# SeptinaryAI_Balldi__elec_mother_board__m.net
KiCad netlist of a schematic drawn in Altium Designer
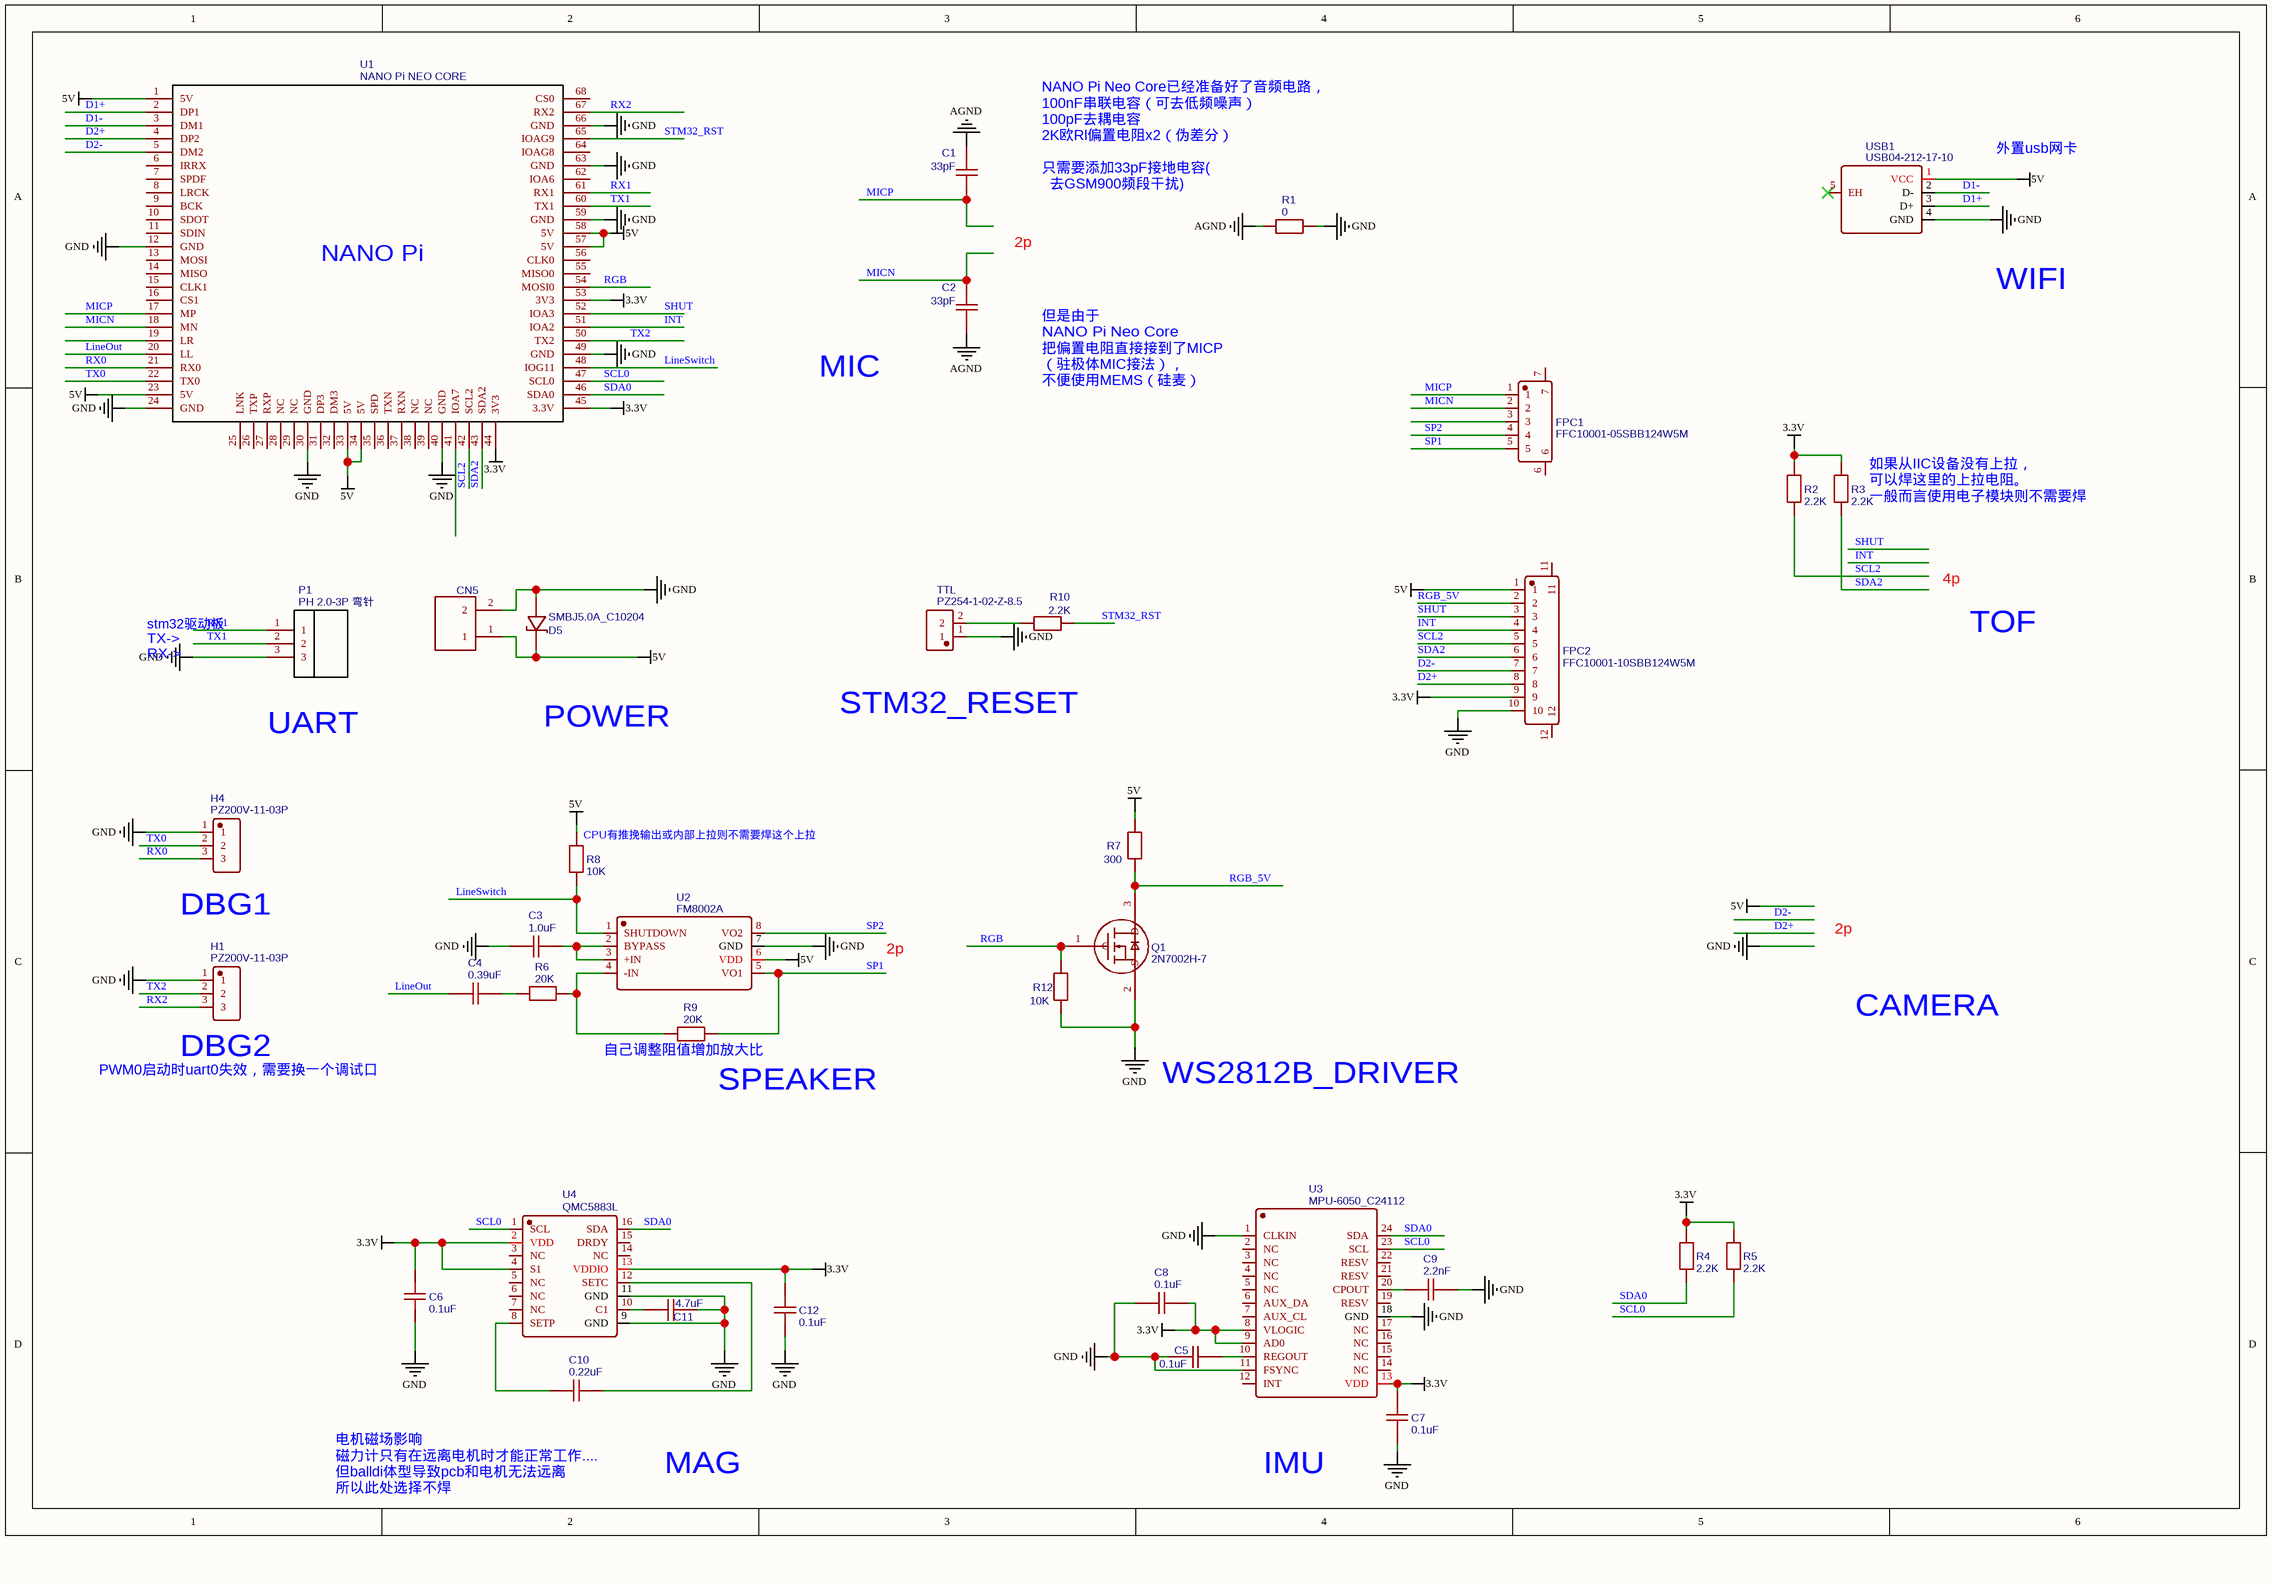
[diagram p0: SeptinaryAI_Balldi__elec_mother_board__mother_board_2023-07-21.schdoc]

(export (version "E")
  (design (tool "Eeschema 10.0.6"))
  (components
    (comp (ref "C1")
      (value "33pF")
      (fields
        (field (name "BOM_SUPPLIER PART") "C2762283")
        (field (name "BOM_MANUFACTURER PART") "CL10F104ZO8NNNC")
        (field (name "CONTRIBUTOR") "LCSC")
      )
      (libsource (lib "altium-import") (part "root_1_33pF_"))
    )
    (comp (ref "C2")
      (value "33pF")
      (fields
        (field (name "BOM_SUPPLIER PART") "C2762283")
        (field (name "BOM_MANUFACTURER PART") "CL10F104ZO8NNNC")
        (field (name "CONTRIBUTOR") "LCSC")
      )
      (libsource (lib "altium-import") (part "root_1_33pF_"))
    )
    (comp (ref "C3")
      (value "1.0uF")
      (fields
        (field (name "BOM_SUPPLIER PART") "C2762283")
        (field (name "BOM_MANUFACTURER PART") "CL10F104ZO8NNNC")
        (field (name "CONTRIBUTOR") "LCSC")
      )
      (libsource (lib "altium-import") (part "root_2_1.0uF_"))
    )
    (comp (ref "C4")
      (value "0.39uF")
      (fields
        (field (name "BOM_SUPPLIER PART") "C2762283")
        (field (name "BOM_MANUFACTURER PART") "CL10F104ZO8NNNC")
        (field (name "CONTRIBUTOR") "LCSC")
      )
      (libsource (lib "altium-import") (part "root_2_0.39uF_"))
    )
    (comp (ref "C5")
      (value "0.1uF")
      (fields
        (field (name "BOM_SUPPLIER PART") "C2762283")
        (field (name "BOM_MANUFACTURER PART") "CL10F104ZO8NNNC")
        (field (name "CONTRIBUTOR") "LCSC")
      )
      (libsource (lib "altium-import") (part "root_2_0.1uF_"))
    )
    (comp (ref "C6")
      (value "0.1uF")
      (fields
        (field (name "BOM_SUPPLIER PART") "C2762283")
        (field (name "BOM_MANUFACTURER PART") "CL10F104ZO8NNNC")
        (field (name "CONTRIBUTOR") "LCSC")
      )
      (libsource (lib "altium-import") (part "root_3_0.1uF_"))
    )
    (comp (ref "C7")
      (value "0.1uF")
      (fields
        (field (name "BOM_SUPPLIER PART") "C2762283")
        (field (name "BOM_MANUFACTURER PART") "CL10F104ZO8NNNC")
        (field (name "CONTRIBUTOR") "LCSC")
      )
      (libsource (lib "altium-import") (part "root_3_0.1uF_"))
    )
    (comp (ref "C8")
      (value "0.1uF")
      (fields
        (field (name "BOM_SUPPLIER PART") "C2762283")
        (field (name "BOM_MANUFACTURER PART") "CL10F104ZO8NNNC")
        (field (name "CONTRIBUTOR") "LCSC")
      )
      (libsource (lib "altium-import") (part "root_0_0.1uF_"))
    )
    (comp (ref "C9")
      (value "2.2nF")
      (fields
        (field (name "BOM_SUPPLIER PART") "C2762283")
        (field (name "BOM_MANUFACTURER PART") "CL10F104ZO8NNNC")
        (field (name "CONTRIBUTOR") "LCSC")
      )
      (libsource (lib "altium-import") (part "root_0_2.2nF_"))
    )
    (comp (ref "C10")
      (value "0.22uF")
      (fields
        (field (name "BOM_SUPPLIER PART") "C2762283")
        (field (name "BOM_MANUFACTURER PART") "CL10F104ZO8NNNC")
        (field (name "CONTRIBUTOR") "LCSC")
      )
      (libsource (lib "altium-import") (part "root_0_0.22uF_"))
    )
    (comp (ref "C11")
      (value "4.7uF")
      (fields
        (field (name "BOM_SUPPLIER PART") "C2762283")
        (field (name "BOM_MANUFACTURER PART") "CL10F104ZO8NNNC")
        (field (name "CONTRIBUTOR") "LCSC")
      )
      (libsource (lib "altium-import") (part "root_0_4.7uF_"))
    )
    (comp (ref "C12")
      (value "0.1uF")
      (fields
        (field (name "BOM_SUPPLIER PART") "C2762283")
        (field (name "BOM_MANUFACTURER PART") "CL10F104ZO8NNNC")
        (field (name "CONTRIBUTOR") "LCSC")
      )
      (libsource (lib "altium-import") (part "root_3_0.1uF_"))
    )
    (comp (ref "CN5")
      (value "640454-2")
      (fields (field (name "BOM_SUPPLIER PART") "C86501"))
      (libsource (lib "altium-import") (part "root_2_640454-2_"))
    )
    (comp (ref "D5")
      (value "SMBJ5.0A_C10204")
      (fields (field (name "BOM_MANUFACTURER PART") "SMBJ5.0A") (field (name "BOM_SUPPLIER PART") "C10204"))
      (libsource (lib "altium-import") (part "root_1_SMBJ5.0A_C10204_"))
    )
    (comp (ref "FPC1")
      (value "FFC10001-05SBB124W5M")
      (fields (field (name "BOM_SUPPLIER PART") "C2833987") (field (name "CONTRIBUTOR") "LCSC"))
      (libsource (lib "altium-import") (part "root_0_FFC10001-05SBB124W5M_"))
    )
    (comp (ref "FPC2")
      (value "FFC10001-10SBB124W5M")
      (fields (field (name "BOM_SUPPLIER PART") "C456461") (field (name "CONTRIBUTOR") "LCSC"))
      (libsource (lib "altium-import") (part "root_0_FFC10001-10SBB124W5M_"))
    )
    (comp (ref "H1")
      (value "PZ200V-11-03P")
      (fields (field (name "BOM_SUPPLIER PART") "C541857") (field (name "CONTRIBUTOR") "LCSC"))
      (libsource (lib "altium-import") (part "root_0_PZ200V-11-03P_"))
    )
    (comp (ref "H4")
      (value "PZ200V-11-03P")
      (fields (field (name "BOM_SUPPLIER PART") "C541857") (field (name "CONTRIBUTOR") "LCSC"))
      (libsource (lib "altium-import") (part "root_0_PZ200V-11-03P_"))
    )
    (comp (ref "P1")
      (value "PH 2.0-3P 弯针")
      (fields (field (name "BOM_MANUFACTURER PART") "PH 2.0-3P") (field (name "CONTRIBUTOR") "584992092"))
      (libsource (lib "altium-import") (part "root_3_PH 2.0-3P 弯针_"))
    )
    (comp (ref "Q1")
      (value "2N7002H-7")
      (fields (field (name "BOM_SUPPLIER PART") "C150714") (field (name "CONTRIBUTOR") "LCSC"))
      (libsource (lib "altium-import") (part "root_0_2N7002H-7_"))
    )
    (comp (ref "R1")
      (value "0")
      (fields
        (field (name "BOM_SUPPLIER PART") "C1870287")
        (field (name "BOM_MANUFACTURER PART") "TNPW0603130RBEEA")
        (field (name "CONTRIBUTOR") "LCSC")
      )
      (libsource (lib "altium-import") (part "root_0_0_"))
    )
    (comp (ref "R2")
      (value "2.2K")
      (fields
        (field (name "BOM_SUPPLIER PART") "C1870287")
        (field (name "BOM_MANUFACTURER PART") "TNPW0603130RBEEA")
        (field (name "CONTRIBUTOR") "LCSC")
      )
      (libsource (lib "altium-import") (part "root_3_2.2K_"))
    )
    (comp (ref "R3")
      (value "2.2K")
      (fields
        (field (name "BOM_SUPPLIER PART") "C1870287")
        (field (name "BOM_MANUFACTURER PART") "TNPW0603130RBEEA")
        (field (name "CONTRIBUTOR") "LCSC")
      )
      (libsource (lib "altium-import") (part "root_3_2.2K_"))
    )
    (comp (ref "R4")
      (value "2.2K")
      (fields
        (field (name "BOM_SUPPLIER PART") "C1870287")
        (field (name "BOM_MANUFACTURER PART") "TNPW0603130RBEEA")
        (field (name "CONTRIBUTOR") "LCSC")
      )
      (libsource (lib "altium-import") (part "root_3_2.2K_"))
    )
    (comp (ref "R5")
      (value "2.2K")
      (fields
        (field (name "BOM_SUPPLIER PART") "C1870287")
        (field (name "BOM_MANUFACTURER PART") "TNPW0603130RBEEA")
        (field (name "CONTRIBUTOR") "LCSC")
      )
      (libsource (lib "altium-import") (part "root_3_2.2K_"))
    )
    (comp (ref "R6")
      (value "20K")
      (fields
        (field (name "BOM_SUPPLIER PART") "C1870287")
        (field (name "BOM_MANUFACTURER PART") "TNPW0603130RBEEA")
        (field (name "CONTRIBUTOR") "LCSC")
      )
      (libsource (lib "altium-import") (part "root_0_20K_"))
    )
    (comp (ref "R7")
      (value "300")
      (fields
        (field (name "BOM_SUPPLIER PART") "C1870287")
        (field (name "BOM_MANUFACTURER PART") "TNPW0603130RBEEA")
        (field (name "CONTRIBUTOR") "LCSC")
      )
      (libsource (lib "altium-import") (part "root_3_300_"))
    )
    (comp (ref "R8")
      (value "10K")
      (fields
        (field (name "BOM_SUPPLIER PART") "C1870287")
        (field (name "BOM_MANUFACTURER PART") "TNPW0603130RBEEA")
        (field (name "CONTRIBUTOR") "LCSC")
      )
      (libsource (lib "altium-import") (part "root_1_10K_"))
    )
    (comp (ref "R9")
      (value "20K")
      (fields
        (field (name "BOM_SUPPLIER PART") "C1870287")
        (field (name "BOM_MANUFACTURER PART") "TNPW0603130RBEEA")
        (field (name "CONTRIBUTOR") "LCSC")
      )
      (libsource (lib "altium-import") (part "root_0_20K_"))
    )
    (comp (ref "R10")
      (value "2.2K")
      (fields
        (field (name "BOM_SUPPLIER PART") "C1870287")
        (field (name "BOM_MANUFACTURER PART") "TNPW0603130RBEEA")
        (field (name "CONTRIBUTOR") "LCSC")
      )
      (libsource (lib "altium-import") (part "root_0_2.2K_"))
    )
    (comp (ref "R12")
      (value "10K")
      (fields
        (field (name "BOM_SUPPLIER PART") "C1870287")
        (field (name "BOM_MANUFACTURER PART") "TNPW0603130RBEEA")
        (field (name "CONTRIBUTOR") "LCSC")
      )
      (libsource (lib "altium-import") (part "root_3_10K_"))
    )
    (comp (ref "TTL")
      (value "PZ254-1-02-Z-8.5")
      (fields (field (name "BOM_SUPPLIER PART") "C2894925") (field (name "CONTRIBUTOR") "jiutianlanyue"))
      (libsource (lib "altium-import") (part "root_0_PZ254-1-02-Z-8.5_"))
    )
    (comp (ref "U1")
      (value "NANO Pi NEO CORE")
      (fields (field (name "CONTRIBUTOR") "sepai"))
      (libsource (lib "altium-import") (part "root_0_NANO Pi NEO CORE_"))
    )
    (comp (ref "U2")
      (value "FM8002A")
      (fields (field (name "BOM_SUPPLIER PART") "C94625"))
      (libsource (lib "altium-import") (part "root_0_FM8002A_"))
    )
    (comp (ref "U3")
      (value "MPU-6050_C24112")
      (fields (field (name "BOM_MANUFACTURER PART") "MPU-6050") (field (name "BOM_SUPPLIER PART") "C24112"))
      (libsource (lib "altium-import") (part "root_0_MPU-6050_C24112_"))
    )
    (comp (ref "U4")
      (value "QMC5883L")
      (fields (field (name "BOM_SUPPLIER PART") "C976032") (field (name "CONTRIBUTOR") "LCSC"))
      (libsource (lib "altium-import") (part "root_0_QMC5883L_"))
    )
    (comp (ref "USB1")
      (value "USB04-212-17-10")
      (fields (field (name "BOM_SUPPLIER PART") "C718030") (field (name "CONTRIBUTOR") "LCSC"))
      (libsource (lib "altium-import") (part "root_0_USB04-212-17-10_"))
    )
  )
  (nets
    (net (code "1") (name "/D1+") (class "Default")
      (node (ref "U1") (pin "2") (pinfunction "DP1_2") (pintype "passive"))
      (node (ref "USB1") (pin "3") (pinfunction "D+_3") (pintype "passive"))
    )
    (net (code "2") (name "/D1-") (class "Default")
      (node (ref "U1") (pin "3") (pinfunction "DM1_3") (pintype "passive"))
      (node (ref "USB1") (pin "2") (pinfunction "D-_2") (pintype "passive"))
    )
    (net (code "3") (name "/D2+") (class "Default")
      (node (ref "FPC2") (pin "8") (pinfunction "8_8") (pintype "passive"))
      (node (ref "U1") (pin "4") (pinfunction "DP2_4") (pintype "passive"))
    )
    (net (code "4") (name "/D2-") (class "Default")
      (node (ref "FPC2") (pin "7") (pinfunction "7_7") (pintype "passive"))
      (node (ref "U1") (pin "5") (pinfunction "DM2_5") (pintype "passive"))
    )
    (net (code "5") (name "/INT") (class "Default")
      (node (ref "FPC2") (pin "4") (pinfunction "4_4") (pintype "passive"))
      (node (ref "U1") (pin "51") (pinfunction "IOA2_51") (pintype "passive"))
    )
    (net (code "6") (name "/LineOut") (class "Default")
      (node (ref "C4") (pin "2") (pinfunction "2_2") (pintype "passive"))
      (node (ref "U1") (pin "20") (pinfunction "LL_20") (pintype "passive"))
    )
    (net (code "7") (name "/LineSwitch") (class "Default")
      (node (ref "R8") (pin "1") (pinfunction "1_1") (pintype "passive"))
      (node (ref "U1") (pin "48") (pinfunction "IOG11_48") (pintype "passive"))
      (node (ref "U2") (pin "1") (pinfunction "SHUTDOWN_1") (pintype "passive"))
    )
    (net (code "8") (name "/MICN") (class "Default")
      (node (ref "C2") (pin "2") (pinfunction "2_2") (pintype "passive"))
      (node (ref "FPC1") (pin "2") (pinfunction "2_2") (pintype "passive"))
      (node (ref "U1") (pin "18") (pinfunction "MN_18") (pintype "passive"))
    )
    (net (code "9") (name "/MICP") (class "Default")
      (node (ref "C1") (pin "1") (pinfunction "1_1") (pintype "passive"))
      (node (ref "FPC1") (pin "1") (pinfunction "1_1") (pintype "passive"))
      (node (ref "U1") (pin "17") (pinfunction "MP_17") (pintype "passive"))
    )
    (net (code "10") (name "/RGB") (class "Default")
      (node (ref "Q1") (pin "1") (pinfunction "G_1") (pintype "passive"))
      (node (ref "R12") (pin "1") (pinfunction "1_1") (pintype "passive"))
      (node (ref "U1") (pin "54") (pinfunction "MOSI0_54") (pintype "passive"))
    )
    (net (code "11") (name "/RGB_5V") (class "Default")
      (node (ref "FPC2") (pin "2") (pinfunction "2_2") (pintype "passive"))
      (node (ref "Q1") (pin "3") (pinfunction "D_3") (pintype "passive"))
      (node (ref "R7") (pin "2") (pinfunction "2_2") (pintype "passive"))
    )
    (net (code "12") (name "/RX0") (class "Default")
      (node (ref "H4") (pin "3") (pinfunction "3_3") (pintype "passive"))
      (node (ref "U1") (pin "21") (pinfunction "RX0_21") (pintype "passive"))
    )
    (net (code "13") (name "/RX1") (class "Default")
      (node (ref "P1") (pin "1") (pinfunction "1_1") (pintype "passive"))
      (node (ref "U1") (pin "61") (pinfunction "RX1_61") (pintype "passive"))
    )
    (net (code "14") (name "/RX2") (class "Default")
      (node (ref "H1") (pin "3") (pinfunction "3_3") (pintype "passive"))
      (node (ref "U1") (pin "67") (pinfunction "RX2_67") (pintype "passive"))
    )
    (net (code "15") (name "/SCL0") (class "Default")
      (node (ref "R5") (pin "2") (pinfunction "2_2") (pintype "passive"))
      (node (ref "U1") (pin "47") (pinfunction "SCL0_47") (pintype "passive"))
      (node (ref "U3") (pin "23") (pinfunction "SCL_23") (pintype "passive"))
      (node (ref "U4") (pin "1") (pinfunction "SCL_1") (pintype "passive"))
    )
    (net (code "16") (name "/SCL2") (class "Default")
      (node (ref "FPC2") (pin "5") (pinfunction "5_5") (pintype "passive"))
      (node (ref "R2") (pin "2") (pinfunction "2_2") (pintype "passive"))
      (node (ref "U1") (pin "42") (pinfunction "SCL2_42") (pintype "passive"))
    )
    (net (code "17") (name "/SDA0") (class "Default")
      (node (ref "R4") (pin "2") (pinfunction "2_2") (pintype "passive"))
      (node (ref "U1") (pin "46") (pinfunction "SDA0_46") (pintype "passive"))
      (node (ref "U3") (pin "24") (pinfunction "SDA_24") (pintype "passive"))
      (node (ref "U4") (pin "16") (pinfunction "SDA_16") (pintype "passive"))
    )
    (net (code "18") (name "/SDA2") (class "Default")
      (node (ref "FPC2") (pin "6") (pinfunction "6_6") (pintype "passive"))
      (node (ref "R3") (pin "2") (pinfunction "2_2") (pintype "passive"))
      (node (ref "U1") (pin "43") (pinfunction "SDA2_43") (pintype "passive"))
    )
    (net (code "19") (name "/SHUT") (class "Default")
      (node (ref "FPC2") (pin "3") (pinfunction "3_3") (pintype "passive"))
      (node (ref "U1") (pin "52") (pinfunction "IOA3_52") (pintype "passive"))
    )
    (net (code "20") (name "/SP1") (class "Default")
      (node (ref "FPC1") (pin "5") (pinfunction "5_5") (pintype "passive"))
      (node (ref "R9") (pin "2") (pinfunction "2_2") (pintype "passive"))
      (node (ref "U2") (pin "5") (pinfunction "VO1_5") (pintype "passive"))
    )
    (net (code "21") (name "/SP2") (class "Default")
      (node (ref "FPC1") (pin "4") (pinfunction "4_4") (pintype "passive"))
      (node (ref "U2") (pin "8") (pinfunction "VO2_8") (pintype "passive"))
    )
    (net (code "22") (name "/STM32_RST") (class "Default")
      (node (ref "R10") (pin "2") (pinfunction "2_2") (pintype "passive"))
      (node (ref "U1") (pin "65") (pinfunction "IOAG9_65") (pintype "passive"))
    )
    (net (code "23") (name "/TX0") (class "Default")
      (node (ref "H4") (pin "2") (pinfunction "2_2") (pintype "passive"))
      (node (ref "U1") (pin "22") (pinfunction "TX0_22") (pintype "passive"))
    )
    (net (code "24") (name "/TX1") (class "Default")
      (node (ref "P1") (pin "2") (pinfunction "2_2") (pintype "passive"))
      (node (ref "U1") (pin "60") (pinfunction "TX1_60") (pintype "passive"))
    )
    (net (code "25") (name "/TX2") (class "Default")
      (node (ref "H1") (pin "2") (pinfunction "2_2") (pintype "passive"))
      (node (ref "U1") (pin "50") (pinfunction "TX2_50") (pintype "passive"))
    )
    (net (code "26") (name "3.3V") (class "Default")
      (node (ref "C12") (pin "1") (pinfunction "1_1") (pintype "passive"))
      (node (ref "C6") (pin "1") (pinfunction "1_1") (pintype "passive"))
      (node (ref "C7") (pin "1") (pinfunction "1_1") (pintype "passive"))
      (node (ref "C8") (pin "2") (pinfunction "2_2") (pintype "passive"))
      (node (ref "FPC2") (pin "9") (pinfunction "9_9") (pintype "passive"))
      (node (ref "R2") (pin "1") (pinfunction "1_1") (pintype "passive"))
      (node (ref "R3") (pin "1") (pinfunction "1_1") (pintype "passive"))
      (node (ref "R4") (pin "1") (pinfunction "1_1") (pintype "passive"))
      (node (ref "R5") (pin "1") (pinfunction "1_1") (pintype "passive"))
      (node (ref "U1") (pin "44") (pinfunction "3V3_44") (pintype "passive"))
      (node (ref "U1") (pin "45") (pinfunction "3.3V_45") (pintype "passive"))
      (node (ref "U1") (pin "53") (pinfunction "3V3_53") (pintype "passive"))
      (node (ref "U3") (pin "13") (pinfunction "VDD_13") (pintype "passive"))
      (node (ref "U3") (pin "8") (pinfunction "VLOGIC_8") (pintype "passive"))
      (node (ref "U3") (pin "9") (pinfunction "AD0_9") (pintype "passive"))
      (node (ref "U4") (pin "13") (pinfunction "VDDIO_13") (pintype "passive"))
      (node (ref "U4") (pin "2") (pinfunction "VDD_2") (pintype "passive"))
      (node (ref "U4") (pin "4") (pinfunction "S1_4") (pintype "passive"))
    )
    (net (code "27") (name "5V") (class "Default")
      (node (ref "CN5") (pin "1") (pinfunction "1_1") (pintype "passive"))
      (node (ref "D5") (pin "2") (pinfunction "K_2") (pintype "passive"))
      (node (ref "FPC2") (pin "1") (pinfunction "1_1") (pintype "passive"))
      (node (ref "R7") (pin "1") (pinfunction "1_1") (pintype "passive"))
      (node (ref "R8") (pin "2") (pinfunction "2_2") (pintype "passive"))
      (node (ref "U1") (pin "1") (pinfunction "5V_1") (pintype "passive"))
      (node (ref "U1") (pin "23") (pinfunction "5V_23") (pintype "passive"))
      (node (ref "U1") (pin "33") (pinfunction "5V_33") (pintype "passive"))
      (node (ref "U1") (pin "34") (pinfunction "5V_34") (pintype "passive"))
      (node (ref "U1") (pin "57") (pinfunction "5V_57") (pintype "passive"))
      (node (ref "U1") (pin "58") (pinfunction "5V_58") (pintype "passive"))
      (node (ref "U2") (pin "6") (pinfunction "VDD_6") (pintype "passive"))
      (node (ref "USB1") (pin "1") (pinfunction "VCC_1") (pintype "passive"))
    )
    (net (code "28") (name "AGND") (class "Default")
      (node (ref "C1") (pin "2") (pinfunction "2_2") (pintype "passive"))
      (node (ref "C2") (pin "1") (pinfunction "1_1") (pintype "passive"))
      (node (ref "R1") (pin "1") (pinfunction "1_1") (pintype "passive"))
    )
    (net (code "29") (name "GND") (class "Default")
      (node (ref "C11") (pin "2") (pinfunction "2_2") (pintype "passive"))
      (node (ref "C12") (pin "2") (pinfunction "2_2") (pintype "passive"))
      (node (ref "C3") (pin "2") (pinfunction "2_2") (pintype "passive"))
      (node (ref "C5") (pin "2") (pinfunction "2_2") (pintype "passive"))
      (node (ref "C6") (pin "2") (pinfunction "2_2") (pintype "passive"))
      (node (ref "C7") (pin "2") (pinfunction "2_2") (pintype "passive"))
      (node (ref "C8") (pin "1") (pinfunction "1_1") (pintype "passive"))
      (node (ref "C9") (pin "2") (pinfunction "2_2") (pintype "passive"))
      (node (ref "CN5") (pin "2") (pinfunction "2_2") (pintype "passive"))
      (node (ref "D5") (pin "1") (pinfunction "A_1") (pintype "passive"))
      (node (ref "FPC2") (pin "10") (pinfunction "10_10") (pintype "passive"))
      (node (ref "H1") (pin "1") (pinfunction "1_1") (pintype "passive"))
      (node (ref "H4") (pin "1") (pinfunction "1_1") (pintype "passive"))
      (node (ref "P1") (pin "3") (pinfunction "3_3") (pintype "passive"))
      (node (ref "Q1") (pin "2") (pinfunction "S_2") (pintype "passive"))
      (node (ref "R1") (pin "2") (pinfunction "2_2") (pintype "passive"))
      (node (ref "R12") (pin "2") (pinfunction "2_2") (pintype "passive"))
      (node (ref "TTL") (pin "1") (pinfunction "1_1") (pintype "passive"))
      (node (ref "U1") (pin "12") (pinfunction "GND_12") (pintype "passive"))
      (node (ref "U1") (pin "24") (pinfunction "GND_24") (pintype "passive"))
      (node (ref "U1") (pin "30") (pinfunction "GND_30") (pintype "passive"))
      (node (ref "U1") (pin "40") (pinfunction "GND_40") (pintype "passive"))
      (node (ref "U1") (pin "49") (pinfunction "GND_49") (pintype "passive"))
      (node (ref "U1") (pin "59") (pinfunction "GND_59") (pintype "passive"))
      (node (ref "U1") (pin "63") (pinfunction "GND_63") (pintype "passive"))
      (node (ref "U1") (pin "66") (pinfunction "GND_66") (pintype "passive"))
      (node (ref "U2") (pin "7") (pinfunction "GND_7") (pintype "passive"))
      (node (ref "U3") (pin "1") (pinfunction "CLKIN_1") (pintype "passive"))
      (node (ref "U3") (pin "11") (pinfunction "FSYNC_11") (pintype "passive"))
      (node (ref "U3") (pin "18") (pinfunction "GND_18") (pintype "passive"))
      (node (ref "U4") (pin "11") (pinfunction "GND_11") (pintype "passive"))
      (node (ref "U4") (pin "9") (pinfunction "GND_9") (pintype "passive"))
      (node (ref "USB1") (pin "4") (pinfunction "GND_4") (pintype "passive"))
    )
    (net (code "30") (name "Net-(C4-Pad1)") (class "Default")
      (node (ref "C4") (pin "1") (pinfunction "1_1") (pintype "passive"))
      (node (ref "R6") (pin "1") (pinfunction "1_1") (pintype "passive"))
    )
    (net (code "31") (name "Net-(R10-Pad1)") (class "Default")
      (node (ref "R10") (pin "1") (pinfunction "1_1") (pintype "passive"))
      (node (ref "TTL") (pin "2") (pinfunction "2_2") (pintype "passive"))
    )
    (net (code "32") (name "Net-(U2-+IN)") (class "Default")
      (node (ref "C3") (pin "1") (pinfunction "1_1") (pintype "passive"))
      (node (ref "U2") (pin "2") (pinfunction "BYPASS_2") (pintype "passive"))
      (node (ref "U2") (pin "3") (pinfunction "+IN_3") (pintype "passive"))
    )
    (net (code "33") (name "Net-(U2--IN)") (class "Default")
      (node (ref "R6") (pin "2") (pinfunction "2_2") (pintype "passive"))
      (node (ref "R9") (pin "1") (pinfunction "1_1") (pintype "passive"))
      (node (ref "U2") (pin "4") (pinfunction "-IN_4") (pintype "passive"))
    )
    (net (code "34") (name "Net-(U3-CPOUT)") (class "Default")
      (node (ref "C9") (pin "1") (pinfunction "1_1") (pintype "passive"))
      (node (ref "U3") (pin "20") (pinfunction "CPOUT_20") (pintype "passive"))
    )
    (net (code "35") (name "Net-(U3-REGOUT)") (class "Default")
      (node (ref "C5") (pin "1") (pinfunction "1_1") (pintype "passive"))
      (node (ref "U3") (pin "10") (pinfunction "REGOUT_10") (pintype "passive"))
    )
    (net (code "36") (name "Net-(U4-C1)") (class "Default")
      (node (ref "C11") (pin "1") (pinfunction "1_1") (pintype "passive"))
      (node (ref "U4") (pin "10") (pinfunction "C1_10") (pintype "passive"))
    )
    (net (code "37") (name "Net-(U4-SETC)") (class "Default")
      (node (ref "C10") (pin "2") (pinfunction "2_2") (pintype "passive"))
      (node (ref "U4") (pin "12") (pinfunction "SETC_12") (pintype "passive"))
    )
    (net (code "38") (name "Net-(U4-SETP)") (class "Default")
      (node (ref "C10") (pin "1") (pinfunction "1_1") (pintype "passive"))
      (node (ref "U4") (pin "8") (pinfunction "SETP_8") (pintype "passive"))
    )
    (net (code "39") (name "unconnected-(FPC1-Pad3)") (class "Default")
      (node (ref "FPC1") (pin "3") (pinfunction "3_3") (pintype "passive"))
    )
    (net (code "40") (name "unconnected-(FPC1-Pad6)") (class "Default")
      (node (ref "FPC1") (pin "6") (pinfunction "6_6") (pintype "passive"))
    )
    (net (code "41") (name "unconnected-(FPC1-Pad7)") (class "Default")
      (node (ref "FPC1") (pin "7") (pinfunction "7_7") (pintype "passive"))
    )
    (net (code "42") (name "unconnected-(FPC2-Pad11)") (class "Default")
      (node (ref "FPC2") (pin "11") (pinfunction "11_11") (pintype "passive"))
    )
    (net (code "43") (name "unconnected-(FPC2-Pad12)") (class "Default")
      (node (ref "FPC2") (pin "12") (pinfunction "12_12") (pintype "passive"))
    )
    (net (code "44") (name "unconnected-(U1-BCK-Pad9)") (class "Default")
      (node (ref "U1") (pin "9") (pinfunction "BCK_9") (pintype "passive"))
    )
    (net (code "45") (name "unconnected-(U1-CLK0-Pad56)") (class "Default")
      (node (ref "U1") (pin "56") (pinfunction "CLK0_56") (pintype "passive"))
    )
    (net (code "46") (name "unconnected-(U1-CLK1-Pad15)") (class "Default")
      (node (ref "U1") (pin "15") (pinfunction "CLK1_15") (pintype "passive"))
    )
    (net (code "47") (name "unconnected-(U1-CS0-Pad68)") (class "Default")
      (node (ref "U1") (pin "68") (pinfunction "CS0_68") (pintype "passive"))
    )
    (net (code "48") (name "unconnected-(U1-CS1-Pad16)") (class "Default")
      (node (ref "U1") (pin "16") (pinfunction "CS1_16") (pintype "passive"))
    )
    (net (code "49") (name "unconnected-(U1-DM3-Pad32)") (class "Default")
      (node (ref "U1") (pin "32") (pinfunction "DM3_32") (pintype "passive"))
    )
    (net (code "50") (name "unconnected-(U1-DP3-Pad31)") (class "Default")
      (node (ref "U1") (pin "31") (pinfunction "DP3_31") (pintype "passive"))
    )
    (net (code "51") (name "unconnected-(U1-IOA6-Pad62)") (class "Default")
      (node (ref "U1") (pin "62") (pinfunction "IOA6_62") (pintype "passive"))
    )
    (net (code "52") (name "unconnected-(U1-IOA7-Pad41)") (class "Default")
      (node (ref "U1") (pin "41") (pinfunction "IOA7_41") (pintype "passive"))
    )
    (net (code "53") (name "unconnected-(U1-IOAG8-Pad64)") (class "Default")
      (node (ref "U1") (pin "64") (pinfunction "IOAG8_64") (pintype "passive"))
    )
    (net (code "54") (name "unconnected-(U1-IRRX-Pad6)") (class "Default")
      (node (ref "U1") (pin "6") (pinfunction "IRRX_6") (pintype "passive"))
    )
    (net (code "55") (name "unconnected-(U1-LNK-Pad25)") (class "Default")
      (node (ref "U1") (pin "25") (pinfunction "LNK_25") (pintype "passive"))
    )
    (net (code "56") (name "unconnected-(U1-LR-Pad19)") (class "Default")
      (node (ref "U1") (pin "19") (pinfunction "LR_19") (pintype "passive"))
    )
    (net (code "57") (name "unconnected-(U1-LRCK-Pad8)") (class "Default")
      (node (ref "U1") (pin "8") (pinfunction "LRCK_8") (pintype "passive"))
    )
    (net (code "58") (name "unconnected-(U1-MISO-Pad14)") (class "Default")
      (node (ref "U1") (pin "14") (pinfunction "MISO_14") (pintype "passive"))
    )
    (net (code "59") (name "unconnected-(U1-MISO0-Pad55)") (class "Default")
      (node (ref "U1") (pin "55") (pinfunction "MISO0_55") (pintype "passive"))
    )
    (net (code "60") (name "unconnected-(U1-MOSI-Pad13)") (class "Default")
      (node (ref "U1") (pin "13") (pinfunction "MOSI_13") (pintype "passive"))
    )
    (net (code "61") (name "unconnected-(U1-NC-Pad28)") (class "Default")
      (node (ref "U1") (pin "28") (pinfunction "NC_28") (pintype "passive"))
    )
    (net (code "62") (name "unconnected-(U1-NC-Pad29)") (class "Default")
      (node (ref "U1") (pin "29") (pinfunction "NC_29") (pintype "passive"))
    )
    (net (code "63") (name "unconnected-(U1-NC-Pad38)") (class "Default")
      (node (ref "U1") (pin "38") (pinfunction "NC_38") (pintype "passive"))
    )
    (net (code "64") (name "unconnected-(U1-NC-Pad39)") (class "Default")
      (node (ref "U1") (pin "39") (pinfunction "NC_39") (pintype "passive"))
    )
    (net (code "65") (name "unconnected-(U1-RXN-Pad37)") (class "Default")
      (node (ref "U1") (pin "37") (pinfunction "RXN_37") (pintype "passive"))
    )
    (net (code "66") (name "unconnected-(U1-RXP-Pad27)") (class "Default")
      (node (ref "U1") (pin "27") (pinfunction "RXP_27") (pintype "passive"))
    )
    (net (code "67") (name "unconnected-(U1-SDIN-Pad11)") (class "Default")
      (node (ref "U1") (pin "11") (pinfunction "SDIN_11") (pintype "passive"))
    )
    (net (code "68") (name "unconnected-(U1-SDOT-Pad10)") (class "Default")
      (node (ref "U1") (pin "10") (pinfunction "SDOT_10") (pintype "passive"))
    )
    (net (code "69") (name "unconnected-(U1-SPD-Pad35)") (class "Default")
      (node (ref "U1") (pin "35") (pinfunction "SPD_35") (pintype "passive"))
    )
    (net (code "70") (name "unconnected-(U1-SPDF-Pad7)") (class "Default")
      (node (ref "U1") (pin "7") (pinfunction "SPDF_7") (pintype "passive"))
    )
    (net (code "71") (name "unconnected-(U1-TXN-Pad36)") (class "Default")
      (node (ref "U1") (pin "36") (pinfunction "TXN_36") (pintype "passive"))
    )
    (net (code "72") (name "unconnected-(U1-TXP-Pad26)") (class "Default")
      (node (ref "U1") (pin "26") (pinfunction "TXP_26") (pintype "passive"))
    )
    (net (code "73") (name "unconnected-(U3-AUX_CL-Pad7)") (class "Default")
      (node (ref "U3") (pin "7") (pinfunction "AUX_CL_7") (pintype "passive"))
    )
    (net (code "74") (name "unconnected-(U3-AUX_DA-Pad6)") (class "Default")
      (node (ref "U3") (pin "6") (pinfunction "AUX_DA_6") (pintype "passive"))
    )
    (net (code "75") (name "unconnected-(U3-INT-Pad12)") (class "Default")
      (node (ref "U3") (pin "12") (pinfunction "INT_12") (pintype "passive"))
    )
    (net (code "76") (name "unconnected-(U3-NC-Pad2)") (class "Default")
      (node (ref "U3") (pin "2") (pinfunction "NC_2") (pintype "passive"))
    )
    (net (code "77") (name "unconnected-(U3-NC-Pad3)") (class "Default")
      (node (ref "U3") (pin "3") (pinfunction "NC_3") (pintype "passive"))
    )
    (net (code "78") (name "unconnected-(U3-NC-Pad4)") (class "Default")
      (node (ref "U3") (pin "4") (pinfunction "NC_4") (pintype "passive"))
    )
    (net (code "79") (name "unconnected-(U3-NC-Pad5)") (class "Default")
      (node (ref "U3") (pin "5") (pinfunction "NC_5") (pintype "passive"))
    )
    (net (code "80") (name "unconnected-(U3-NC-Pad14)") (class "Default")
      (node (ref "U3") (pin "14") (pinfunction "NC_14") (pintype "passive"))
    )
    (net (code "81") (name "unconnected-(U3-NC-Pad15)") (class "Default")
      (node (ref "U3") (pin "15") (pinfunction "NC_15") (pintype "passive"))
    )
    (net (code "82") (name "unconnected-(U3-NC-Pad16)") (class "Default")
      (node (ref "U3") (pin "16") (pinfunction "NC_16") (pintype "passive"))
    )
    (net (code "83") (name "unconnected-(U3-NC-Pad17)") (class "Default")
      (node (ref "U3") (pin "17") (pinfunction "NC_17") (pintype "passive"))
    )
    (net (code "84") (name "unconnected-(U3-RESV-Pad19)") (class "Default")
      (node (ref "U3") (pin "19") (pinfunction "RESV_19") (pintype "passive"))
    )
    (net (code "85") (name "unconnected-(U3-RESV-Pad21)") (class "Default")
      (node (ref "U3") (pin "21") (pinfunction "RESV_21") (pintype "passive"))
    )
    (net (code "86") (name "unconnected-(U3-RESV-Pad22)") (class "Default")
      (node (ref "U3") (pin "22") (pinfunction "RESV_22") (pintype "passive"))
    )
    (net (code "87") (name "unconnected-(U4-DRDY-Pad15)") (class "Default")
      (node (ref "U4") (pin "15") (pinfunction "DRDY_15") (pintype "passive"))
    )
    (net (code "88") (name "unconnected-(U4-NC-Pad3)") (class "Default")
      (node (ref "U4") (pin "3") (pinfunction "NC_3") (pintype "passive"))
    )
    (net (code "89") (name "unconnected-(U4-NC-Pad5)") (class "Default")
      (node (ref "U4") (pin "5") (pinfunction "NC_5") (pintype "passive"))
    )
    (net (code "90") (name "unconnected-(U4-NC-Pad6)") (class "Default")
      (node (ref "U4") (pin "6") (pinfunction "NC_6") (pintype "passive"))
    )
    (net (code "91") (name "unconnected-(U4-NC-Pad7)") (class "Default")
      (node (ref "U4") (pin "7") (pinfunction "NC_7") (pintype "passive"))
    )
    (net (code "92") (name "unconnected-(U4-NC-Pad14)") (class "Default")
      (node (ref "U4") (pin "14") (pinfunction "NC_14") (pintype "passive"))
    )
    (net (code "93") (name "unconnected-(USB1-EH-Pad5)") (class "Default")
      (node (ref "USB1") (pin "5") (pinfunction "EH_5") (pintype "passive+no_connect"))
    )
  )
)
